# july-10.net
KiCad netlist of a schematic drawn in EAGLE
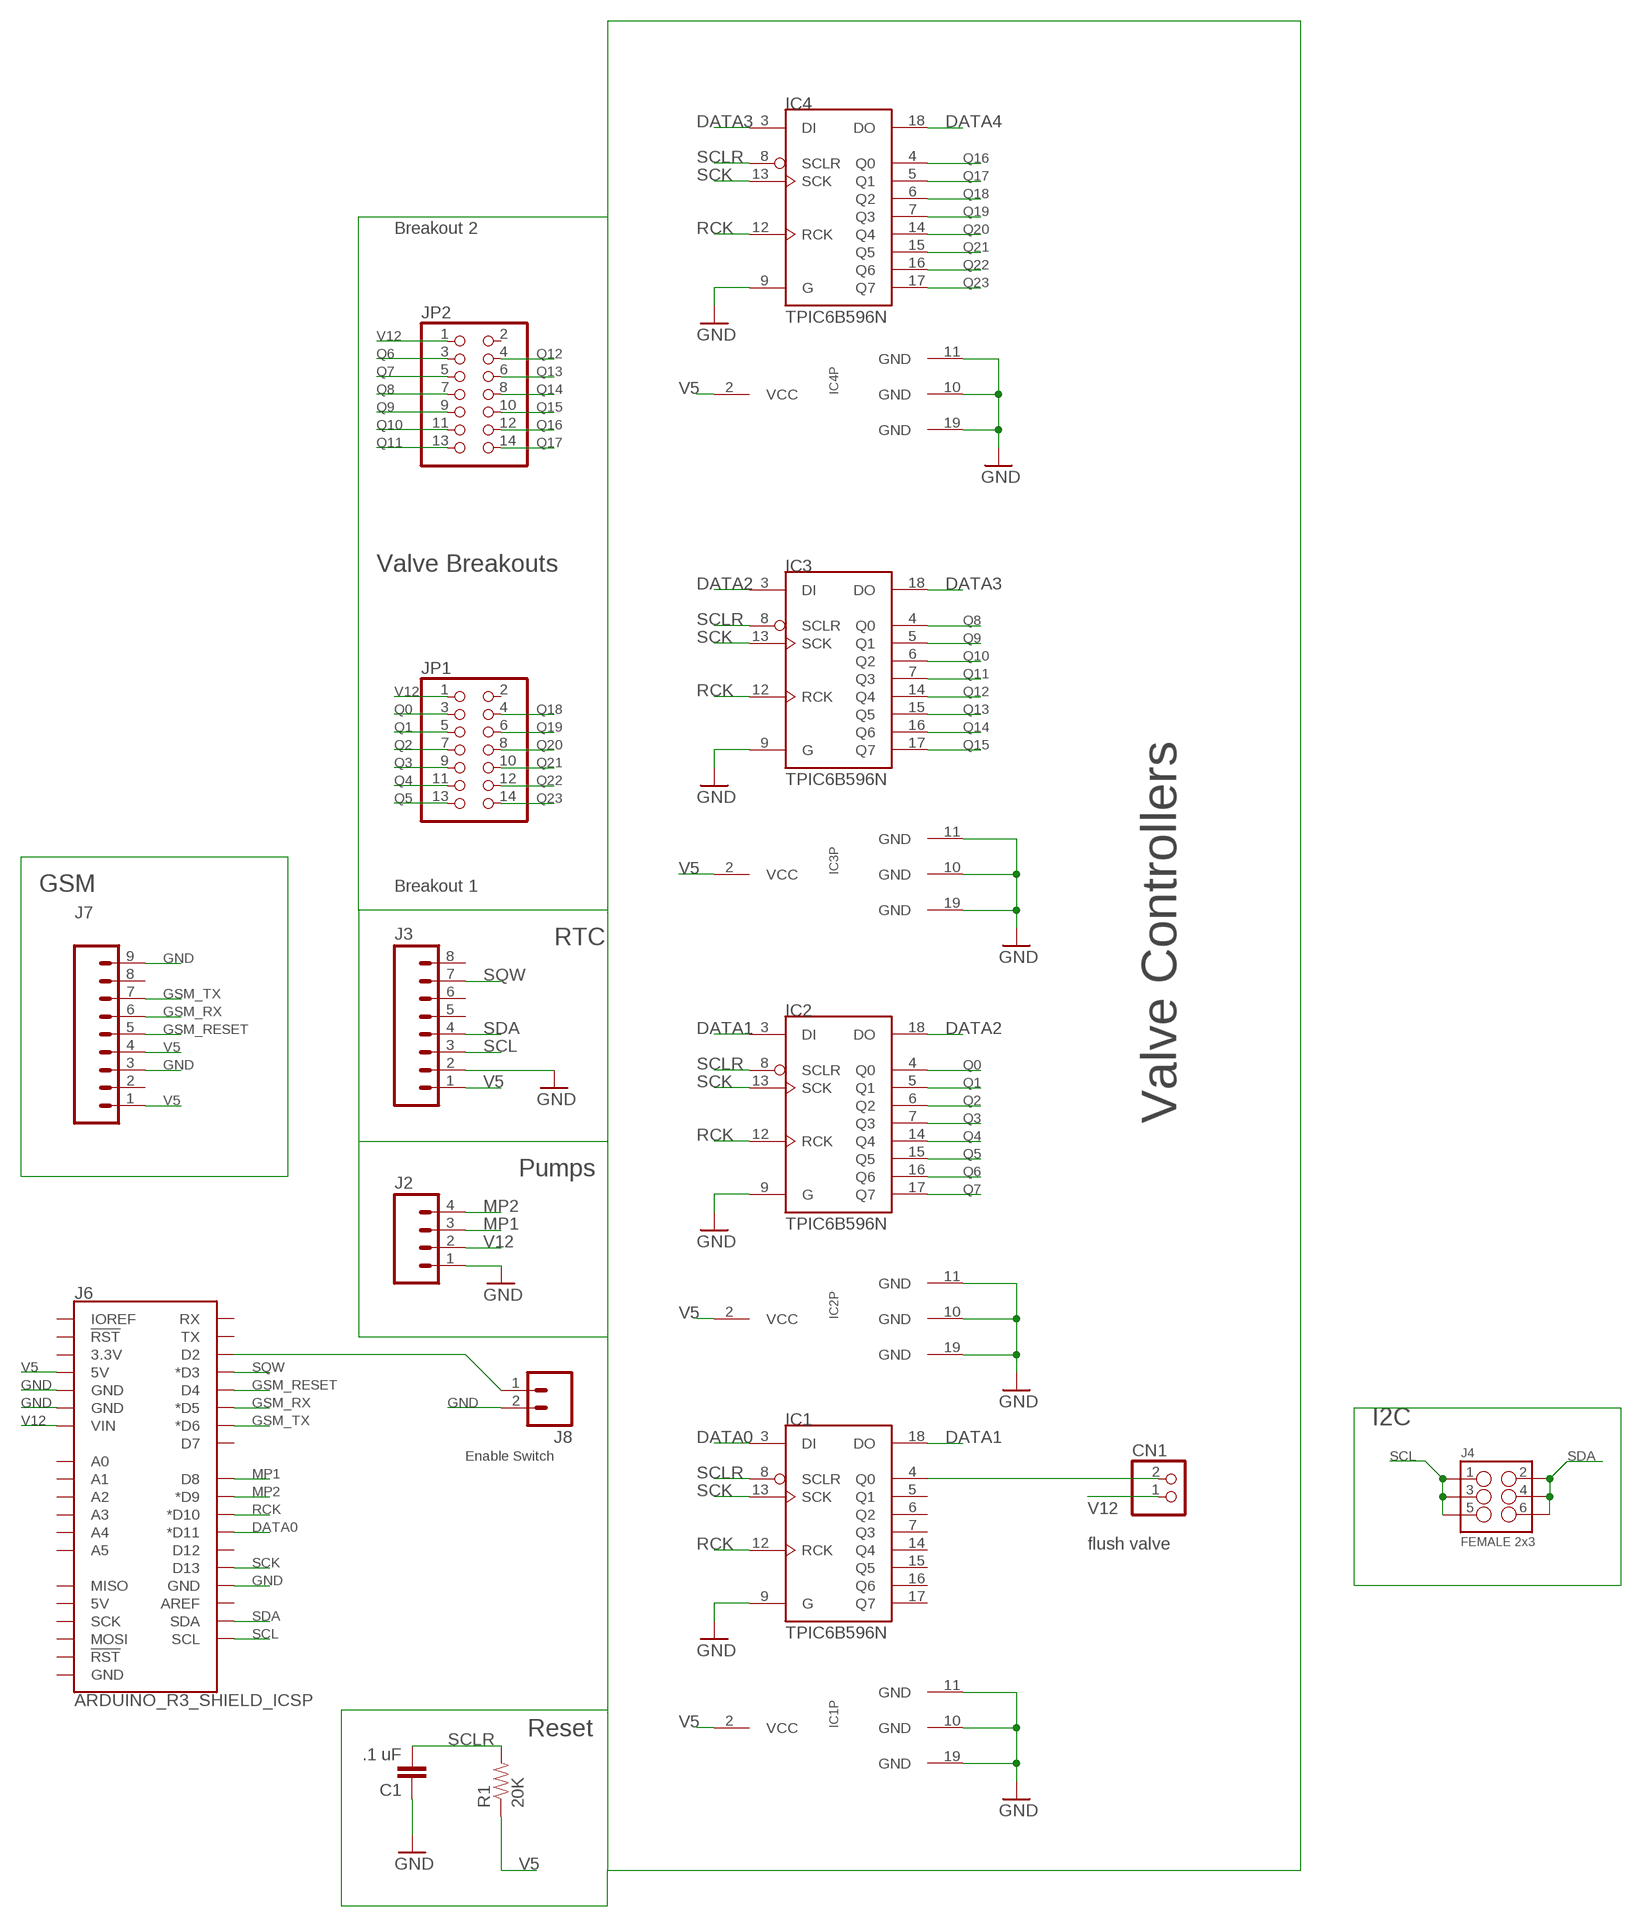
[diagram p0: schematic, sheet 1]

(export (version "E")
  (design (tool "Eeschema 10.0.6"))
  (components
    (comp (ref "C1")
      (value ".1 uF")
      (footprint "eagle-import:AXIAL-5MM")
      (libsource (lib "eagle-import") (part "CAP_"))
    )
    (comp (ref "CN1")
      (value "JST_2PIN-THM")
      (footprint "eagle-import:JST-PH-2-THM")
      (libsource (lib "eagle-import") (part "JST_2PIN-THM"))
    )
    (comp (ref "IC1")
      (value "TPIC6B596N")
      (footprint "eagle-import:DIL20")
      (libsource (lib "eagle-import") (part "TPIC6B596N"))
    )
    (comp (ref "IC2")
      (value "TPIC6B596N")
      (footprint "eagle-import:DIL20")
      (libsource (lib "eagle-import") (part "TPIC6B596N"))
    )
    (comp (ref "IC3")
      (value "TPIC6B596N")
      (footprint "eagle-import:DIL20")
      (libsource (lib "eagle-import") (part "TPIC6B596N"))
    )
    (comp (ref "IC4")
      (value "TPIC6B596N")
      (footprint "eagle-import:DIL20")
      (libsource (lib "eagle-import") (part "TPIC6B596N"))
    )
    (comp (ref "J2")
      (value "M04PTH")
      (footprint "eagle-import:1X04")
      (libsource (lib "eagle-import") (part "M04PTH"))
    )
    (comp (ref "J3")
      (value "M08")
      (footprint "eagle-import:1X08_ROUND")
      (libsource (lib "eagle-import") (part "M08"))
    )
    (comp (ref "J4")
      (value "FEMALE 2x3")
      (footprint "eagle-import:2X3")
      (libsource (lib "eagle-import") (part "M03X2FEMALE"))
    )
    (comp (ref "J6")
      (value "ARDUINO_R3_SHIELD_ICSP")
      (footprint "eagle-import:UNO_R3_SHIELD_ICSP")
      (libsource (lib "eagle-import") (part "ARDUINO_R3_SHIELD_ICSP"))
    )
    (comp (ref "J7")
      (value "M09")
      (footprint "eagle-import:1X09")
      (libsource (lib "eagle-import") (part "M09"))
    )
    (comp (ref "J8")
      (value "M02PTH")
      (footprint "eagle-import:1X02")
      (libsource (lib "eagle-import") (part "M02PTH"))
    )
    (comp (ref "JP1")
      (value "PINHD-2X7")
      (footprint "eagle-import:2X07")
      (libsource (lib "eagle-import") (part "PINHD-2X7"))
    )
    (comp (ref "JP2")
      (value "PINHD-2X7")
      (footprint "eagle-import:2X07")
      (libsource (lib "eagle-import") (part "PINHD-2X7"))
    )
    (comp (ref "R1")
      (value "20K")
      (footprint "eagle-import:AXIAL-0.4")
      (libsource (lib "eagle-import") (part "RESISTORPTH-1/4W"))
    )
  )
  (nets
    (net (code "1") (name "/DATA0") (class "Default")
      (node (ref "IC1") (pin "3") (pinfunction "DI_3") (pintype "input"))
      (node (ref "J6") (pin "D11") (pinfunction "*D11_D11") (pintype "bidirectional"))
    )
    (net (code "2") (name "/DATA1") (class "Default")
      (node (ref "IC1") (pin "18") (pinfunction "DO_18") (pintype "output"))
      (node (ref "IC2") (pin "3") (pinfunction "DI_3") (pintype "input"))
    )
    (net (code "3") (name "/DATA2") (class "Default")
      (node (ref "IC2") (pin "18") (pinfunction "DO_18") (pintype "output"))
      (node (ref "IC3") (pin "3") (pinfunction "DI_3") (pintype "input"))
    )
    (net (code "4") (name "/DATA3") (class "Default")
      (node (ref "IC3") (pin "18") (pinfunction "DO_18") (pintype "output"))
      (node (ref "IC4") (pin "3") (pinfunction "DI_3") (pintype "input"))
    )
    (net (code "5") (name "/DATA4") (class "Default")
      (node (ref "IC4") (pin "18") (pinfunction "DO_18") (pintype "output"))
    )
    (net (code "6") (name "/GSM_RESET") (class "Default")
      (node (ref "J6") (pin "D4") (pinfunction "D4_D4") (pintype "bidirectional"))
      (node (ref "J7") (pin "5") (pinfunction "5_5") (pintype "passive"))
    )
    (net (code "7") (name "/GSM_RX") (class "Default")
      (node (ref "J6") (pin "D5") (pinfunction "*D5_D5") (pintype "bidirectional"))
      (node (ref "J7") (pin "6") (pinfunction "6_6") (pintype "passive"))
    )
    (net (code "8") (name "/GSM_TX") (class "Default")
      (node (ref "J6") (pin "D6") (pinfunction "*D6_D6") (pintype "bidirectional"))
      (node (ref "J7") (pin "7") (pinfunction "7_7") (pintype "passive"))
    )
    (net (code "9") (name "/MP1") (class "Default")
      (node (ref "J2") (pin "3") (pinfunction "3_3") (pintype "passive"))
      (node (ref "J6") (pin "D8") (pinfunction "D8_D8") (pintype "bidirectional"))
    )
    (net (code "10") (name "/MP2") (class "Default")
      (node (ref "J2") (pin "4") (pinfunction "4_4") (pintype "passive"))
      (node (ref "J6") (pin "D9") (pinfunction "*D9_D9") (pintype "bidirectional"))
    )
    (net (code "11") (name "/Q0") (class "Default")
      (node (ref "IC2") (pin "4") (pinfunction "Q0_4") (pintype "open_collector"))
      (node (ref "JP1") (pin "3") (pinfunction "3_3") (pintype "passive"))
    )
    (net (code "12") (name "/Q1") (class "Default")
      (node (ref "IC2") (pin "5") (pinfunction "Q1_5") (pintype "open_collector"))
      (node (ref "JP1") (pin "5") (pinfunction "5_5") (pintype "passive"))
    )
    (net (code "13") (name "/Q2") (class "Default")
      (node (ref "IC2") (pin "6") (pinfunction "Q2_6") (pintype "open_collector"))
      (node (ref "JP1") (pin "7") (pinfunction "7_7") (pintype "passive"))
    )
    (net (code "14") (name "/Q3") (class "Default")
      (node (ref "IC2") (pin "7") (pinfunction "Q3_7") (pintype "open_collector"))
      (node (ref "JP1") (pin "9") (pinfunction "9_9") (pintype "passive"))
    )
    (net (code "15") (name "/Q4") (class "Default")
      (node (ref "IC2") (pin "14") (pinfunction "Q4_14") (pintype "open_collector"))
      (node (ref "JP1") (pin "11") (pinfunction "11_11") (pintype "passive"))
    )
    (net (code "16") (name "/Q5") (class "Default")
      (node (ref "IC2") (pin "15") (pinfunction "Q5_15") (pintype "open_collector"))
      (node (ref "JP1") (pin "13") (pinfunction "13_13") (pintype "passive"))
    )
    (net (code "17") (name "/Q6") (class "Default")
      (node (ref "IC2") (pin "16") (pinfunction "Q6_16") (pintype "open_collector"))
      (node (ref "JP2") (pin "3") (pinfunction "3_3") (pintype "passive"))
    )
    (net (code "18") (name "/Q7") (class "Default")
      (node (ref "IC2") (pin "17") (pinfunction "Q7_17") (pintype "open_collector"))
      (node (ref "JP2") (pin "5") (pinfunction "5_5") (pintype "passive"))
    )
    (net (code "19") (name "/Q8") (class "Default")
      (node (ref "IC3") (pin "4") (pinfunction "Q0_4") (pintype "open_collector"))
      (node (ref "JP2") (pin "7") (pinfunction "7_7") (pintype "passive"))
    )
    (net (code "20") (name "/Q9") (class "Default")
      (node (ref "IC3") (pin "5") (pinfunction "Q1_5") (pintype "open_collector"))
      (node (ref "JP2") (pin "9") (pinfunction "9_9") (pintype "passive"))
    )
    (net (code "21") (name "/Q10") (class "Default")
      (node (ref "IC3") (pin "6") (pinfunction "Q2_6") (pintype "open_collector"))
      (node (ref "JP2") (pin "11") (pinfunction "11_11") (pintype "passive"))
    )
    (net (code "22") (name "/Q11") (class "Default")
      (node (ref "IC3") (pin "7") (pinfunction "Q3_7") (pintype "open_collector"))
      (node (ref "JP2") (pin "13") (pinfunction "13_13") (pintype "passive"))
    )
    (net (code "23") (name "/Q12") (class "Default")
      (node (ref "IC3") (pin "14") (pinfunction "Q4_14") (pintype "open_collector"))
      (node (ref "JP2") (pin "4") (pinfunction "4_4") (pintype "passive"))
    )
    (net (code "24") (name "/Q13") (class "Default")
      (node (ref "IC3") (pin "15") (pinfunction "Q5_15") (pintype "open_collector"))
      (node (ref "JP2") (pin "6") (pinfunction "6_6") (pintype "passive"))
    )
    (net (code "25") (name "/Q14") (class "Default")
      (node (ref "IC3") (pin "16") (pinfunction "Q6_16") (pintype "open_collector"))
      (node (ref "JP2") (pin "8") (pinfunction "8_8") (pintype "passive"))
    )
    (net (code "26") (name "/Q15") (class "Default")
      (node (ref "IC3") (pin "17") (pinfunction "Q7_17") (pintype "open_collector"))
      (node (ref "JP2") (pin "10") (pinfunction "10_10") (pintype "passive"))
    )
    (net (code "27") (name "/Q16") (class "Default")
      (node (ref "IC4") (pin "4") (pinfunction "Q0_4") (pintype "open_collector"))
      (node (ref "JP2") (pin "12") (pinfunction "12_12") (pintype "passive"))
    )
    (net (code "28") (name "/Q17") (class "Default")
      (node (ref "IC4") (pin "5") (pinfunction "Q1_5") (pintype "open_collector"))
      (node (ref "JP2") (pin "14") (pinfunction "14_14") (pintype "passive"))
    )
    (net (code "29") (name "/Q18") (class "Default")
      (node (ref "IC4") (pin "6") (pinfunction "Q2_6") (pintype "open_collector"))
      (node (ref "JP1") (pin "4") (pinfunction "4_4") (pintype "passive"))
    )
    (net (code "30") (name "/Q19") (class "Default")
      (node (ref "IC4") (pin "7") (pinfunction "Q3_7") (pintype "open_collector"))
      (node (ref "JP1") (pin "6") (pinfunction "6_6") (pintype "passive"))
    )
    (net (code "31") (name "/Q20") (class "Default")
      (node (ref "IC4") (pin "14") (pinfunction "Q4_14") (pintype "open_collector"))
      (node (ref "JP1") (pin "8") (pinfunction "8_8") (pintype "passive"))
    )
    (net (code "32") (name "/Q21") (class "Default")
      (node (ref "IC4") (pin "15") (pinfunction "Q5_15") (pintype "open_collector"))
      (node (ref "JP1") (pin "10") (pinfunction "10_10") (pintype "passive"))
    )
    (net (code "33") (name "/Q22") (class "Default")
      (node (ref "IC4") (pin "16") (pinfunction "Q6_16") (pintype "open_collector"))
      (node (ref "JP1") (pin "12") (pinfunction "12_12") (pintype "passive"))
    )
    (net (code "34") (name "/Q23") (class "Default")
      (node (ref "IC4") (pin "17") (pinfunction "Q7_17") (pintype "open_collector"))
      (node (ref "JP1") (pin "14") (pinfunction "14_14") (pintype "passive"))
    )
    (net (code "35") (name "/RCK") (class "Default")
      (node (ref "IC1") (pin "12") (pinfunction "RCK_12") (pintype "input"))
      (node (ref "IC2") (pin "12") (pinfunction "RCK_12") (pintype "input"))
      (node (ref "IC3") (pin "12") (pinfunction "RCK_12") (pintype "input"))
      (node (ref "IC4") (pin "12") (pinfunction "RCK_12") (pintype "input"))
      (node (ref "J6") (pin "D10") (pinfunction "*D10_D10") (pintype "bidirectional"))
    )
    (net (code "36") (name "/SCK") (class "Default")
      (node (ref "IC1") (pin "13") (pinfunction "SCK_13") (pintype "input"))
      (node (ref "IC2") (pin "13") (pinfunction "SCK_13") (pintype "input"))
      (node (ref "IC3") (pin "13") (pinfunction "SCK_13") (pintype "input"))
      (node (ref "IC4") (pin "13") (pinfunction "SCK_13") (pintype "input"))
      (node (ref "J6") (pin "D13") (pinfunction "D13_D13") (pintype "bidirectional"))
    )
    (net (code "37") (name "/SCL") (class "Default")
      (node (ref "J3") (pin "3") (pinfunction "3_3") (pintype "passive"))
      (node (ref "J4") (pin "1") (pinfunction "1_1") (pintype "bidirectional"))
      (node (ref "J4") (pin "3") (pinfunction "3_3") (pintype "bidirectional"))
      (node (ref "J4") (pin "5") (pinfunction "5_5") (pintype "bidirectional"))
      (node (ref "J6") (pin "SCL") (pinfunction "SCL_SCL") (pintype "bidirectional"))
    )
    (net (code "38") (name "/SCLR") (class "Default")
      (node (ref "C1") (pin "P$2") (pinfunction "2_P$2") (pintype "passive"))
      (node (ref "IC1") (pin "8") (pinfunction "SCLR_8") (pintype "input"))
      (node (ref "IC2") (pin "8") (pinfunction "SCLR_8") (pintype "input"))
      (node (ref "IC3") (pin "8") (pinfunction "SCLR_8") (pintype "input"))
      (node (ref "IC4") (pin "8") (pinfunction "SCLR_8") (pintype "input"))
      (node (ref "R1") (pin "P$2") (pinfunction "2_P$2") (pintype "passive"))
    )
    (net (code "39") (name "/SDA") (class "Default")
      (node (ref "J3") (pin "4") (pinfunction "4_4") (pintype "passive"))
      (node (ref "J4") (pin "2") (pinfunction "2_2") (pintype "bidirectional"))
      (node (ref "J4") (pin "4") (pinfunction "4_4") (pintype "bidirectional"))
      (node (ref "J4") (pin "6") (pinfunction "6_6") (pintype "bidirectional"))
      (node (ref "J6") (pin "SDA") (pinfunction "SDA_SDA") (pintype "bidirectional"))
    )
    (net (code "40") (name "/SQW") (class "Default")
      (node (ref "J3") (pin "7") (pinfunction "7_7") (pintype "passive"))
      (node (ref "J6") (pin "D3") (pinfunction "*D3_D3") (pintype "bidirectional"))
    )
    (net (code "41") (name "/V5") (class "Default")
      (node (ref "IC1") (pin "2") (pinfunction "VCC_2") (pintype "power_in"))
      (node (ref "IC2") (pin "2") (pinfunction "VCC_2") (pintype "power_in"))
      (node (ref "IC3") (pin "2") (pinfunction "VCC_2") (pintype "power_in"))
      (node (ref "IC4") (pin "2") (pinfunction "VCC_2") (pintype "power_in"))
      (node (ref "J3") (pin "1") (pinfunction "1_1") (pintype "passive"))
      (node (ref "J6") (pin "5V") (pinfunction "5V_5V") (pintype "bidirectional"))
      (node (ref "J7") (pin "1") (pinfunction "1_1") (pintype "passive"))
      (node (ref "J7") (pin "4") (pinfunction "4_4") (pintype "passive"))
      (node (ref "R1") (pin "P$1") (pinfunction "1_P$1") (pintype "passive"))
    )
    (net (code "42") (name "/V12") (class "Default")
      (node (ref "CN1") (pin "1") (pinfunction "2_1") (pintype "passive"))
      (node (ref "J2") (pin "2") (pinfunction "2_2") (pintype "passive"))
      (node (ref "J6") (pin "VIN") (pinfunction "VIN_VIN") (pintype "bidirectional"))
      (node (ref "JP1") (pin "1") (pinfunction "1_1") (pintype "passive"))
      (node (ref "JP2") (pin "1") (pinfunction "1_1") (pintype "passive"))
    )
    (net (code "43") (name "GND") (class "Default")
      (node (ref "C1") (pin "P$1") (pinfunction "1_P$1") (pintype "passive"))
      (node (ref "IC1") (pin "10") (pinfunction "GND_10") (pintype "power_in"))
      (node (ref "IC1") (pin "11") (pinfunction "GND_11") (pintype "power_in"))
      (node (ref "IC1") (pin "19") (pinfunction "GND_19") (pintype "power_in"))
      (node (ref "IC1") (pin "9") (pinfunction "G_9") (pintype "input"))
      (node (ref "IC2") (pin "10") (pinfunction "GND_10") (pintype "power_in"))
      (node (ref "IC2") (pin "11") (pinfunction "GND_11") (pintype "power_in"))
      (node (ref "IC2") (pin "19") (pinfunction "GND_19") (pintype "power_in"))
      (node (ref "IC2") (pin "9") (pinfunction "G_9") (pintype "input"))
      (node (ref "IC3") (pin "10") (pinfunction "GND_10") (pintype "power_in"))
      (node (ref "IC3") (pin "11") (pinfunction "GND_11") (pintype "power_in"))
      (node (ref "IC3") (pin "19") (pinfunction "GND_19") (pintype "power_in"))
      (node (ref "IC3") (pin "9") (pinfunction "G_9") (pintype "input"))
      (node (ref "IC4") (pin "10") (pinfunction "GND_10") (pintype "power_in"))
      (node (ref "IC4") (pin "11") (pinfunction "GND_11") (pintype "power_in"))
      (node (ref "IC4") (pin "19") (pinfunction "GND_19") (pintype "power_in"))
      (node (ref "IC4") (pin "9") (pinfunction "G_9") (pintype "input"))
      (node (ref "J2") (pin "1") (pinfunction "1_1") (pintype "passive"))
      (node (ref "J3") (pin "2") (pinfunction "2_2") (pintype "passive"))
      (node (ref "J6") (pin "GND@0") (pinfunction "GND_GND@0") (pintype "bidirectional"))
      (node (ref "J6") (pin "GND@1") (pinfunction "GND_GND@1") (pintype "bidirectional"))
      (node (ref "J6") (pin "GND@2") (pinfunction "GND_GND@2") (pintype "bidirectional"))
      (node (ref "J7") (pin "3") (pinfunction "3_3") (pintype "passive"))
      (node (ref "J7") (pin "9") (pinfunction "9_9") (pintype "passive"))
      (node (ref "J8") (pin "2") (pinfunction "2_2") (pintype "passive"))
    )
    (net (code "44") (name "Net-(CN1-1)") (class "Default")
      (node (ref "CN1") (pin "2") (pinfunction "1_2") (pintype "passive"))
      (node (ref "IC1") (pin "4") (pinfunction "Q0_4") (pintype "open_collector"))
    )
    (net (code "45") (name "Net-(J6-PadD2)") (class "Default")
      (node (ref "J6") (pin "D2") (pinfunction "D2_D2") (pintype "bidirectional"))
      (node (ref "J8") (pin "1") (pinfunction "1_1") (pintype "passive"))
    )
    (net (code "46") (name "unconnected-(IC1A-Q1-Pad5)") (class "Default")
      (node (ref "IC1") (pin "5") (pinfunction "Q1_5") (pintype "open_collector"))
    )
    (net (code "47") (name "unconnected-(IC1A-Q2-Pad6)") (class "Default")
      (node (ref "IC1") (pin "6") (pinfunction "Q2_6") (pintype "open_collector"))
    )
    (net (code "48") (name "unconnected-(IC1A-Q3-Pad7)") (class "Default")
      (node (ref "IC1") (pin "7") (pinfunction "Q3_7") (pintype "open_collector"))
    )
    (net (code "49") (name "unconnected-(IC1A-Q4-Pad14)") (class "Default")
      (node (ref "IC1") (pin "14") (pinfunction "Q4_14") (pintype "open_collector"))
    )
    (net (code "50") (name "unconnected-(IC1A-Q5-Pad15)") (class "Default")
      (node (ref "IC1") (pin "15") (pinfunction "Q5_15") (pintype "open_collector"))
    )
    (net (code "51") (name "unconnected-(IC1A-Q6-Pad16)") (class "Default")
      (node (ref "IC1") (pin "16") (pinfunction "Q6_16") (pintype "open_collector"))
    )
    (net (code "52") (name "unconnected-(IC1A-Q7-Pad17)") (class "Default")
      (node (ref "IC1") (pin "17") (pinfunction "Q7_17") (pintype "open_collector"))
    )
    (net (code "53") (name "unconnected-(J3-Pad5)") (class "Default")
      (node (ref "J3") (pin "5") (pinfunction "5_5") (pintype "passive"))
    )
    (net (code "54") (name "unconnected-(J3-Pad6)") (class "Default")
      (node (ref "J3") (pin "6") (pinfunction "6_6") (pintype "passive"))
    )
    (net (code "55") (name "unconnected-(J3-Pad8)") (class "Default")
      (node (ref "J3") (pin "8") (pinfunction "8_8") (pintype "passive"))
    )
    (net (code "56") (name "unconnected-(J6-5V-Pad5V_ICSP)") (class "Default")
      (node (ref "J6") (pin "5V_ICSP") (pinfunction "5V_5V_ICSP") (pintype "bidirectional"))
    )
    (net (code "57") (name "unconnected-(J6-GND-PadGND_ICSP)") (class "Default")
      (node (ref "J6") (pin "GND_ICSP") (pinfunction "GND_GND_ICSP") (pintype "bidirectional"))
    )
    (net (code "58") (name "unconnected-(J6-Pad3.3V)") (class "Default")
      (node (ref "J6") (pin "3.3V") (pinfunction "3.3V_3.3V") (pintype "bidirectional"))
    )
    (net (code "59") (name "unconnected-(J6-PadA0)") (class "Default")
      (node (ref "J6") (pin "A0") (pinfunction "A0_A0") (pintype "bidirectional"))
    )
    (net (code "60") (name "unconnected-(J6-PadA1)") (class "Default")
      (node (ref "J6") (pin "A1") (pinfunction "A1_A1") (pintype "bidirectional"))
    )
    (net (code "61") (name "unconnected-(J6-PadA2)") (class "Default")
      (node (ref "J6") (pin "A2") (pinfunction "A2_A2") (pintype "bidirectional"))
    )
    (net (code "62") (name "unconnected-(J6-PadA3)") (class "Default")
      (node (ref "J6") (pin "A3") (pinfunction "A3_A3") (pintype "bidirectional"))
    )
    (net (code "63") (name "unconnected-(J6-PadA4)") (class "Default")
      (node (ref "J6") (pin "A4") (pinfunction "A4_A4") (pintype "bidirectional"))
    )
    (net (code "64") (name "unconnected-(J6-PadA5)") (class "Default")
      (node (ref "J6") (pin "A5") (pinfunction "A5_A5") (pintype "bidirectional"))
    )
    (net (code "65") (name "unconnected-(J6-PadAREF)") (class "Default")
      (node (ref "J6") (pin "AREF") (pinfunction "AREF_AREF") (pintype "bidirectional"))
    )
    (net (code "66") (name "unconnected-(J6-PadD7)") (class "Default")
      (node (ref "J6") (pin "D7") (pinfunction "D7_D7") (pintype "bidirectional"))
    )
    (net (code "67") (name "unconnected-(J6-PadD12)") (class "Default")
      (node (ref "J6") (pin "D12") (pinfunction "D12_D12") (pintype "bidirectional"))
    )
    (net (code "68") (name "unconnected-(J6-PadIOREF)") (class "Default")
      (node (ref "J6") (pin "IOREF") (pinfunction "IOREF_IOREF") (pintype "bidirectional"))
    )
    (net (code "69") (name "unconnected-(J6-PadMISO)") (class "Default")
      (node (ref "J6") (pin "MISO") (pinfunction "MISO_MISO") (pintype "bidirectional"))
    )
    (net (code "70") (name "unconnected-(J6-PadMOSI)") (class "Default")
      (node (ref "J6") (pin "MOSI") (pinfunction "MOSI_MOSI") (pintype "bidirectional"))
    )
    (net (code "71") (name "unconnected-(J6-PadRX)") (class "Default")
      (node (ref "J6") (pin "RX") (pinfunction "RX_RX") (pintype "bidirectional"))
    )
    (net (code "72") (name "unconnected-(J6-PadSCK)") (class "Default")
      (node (ref "J6") (pin "SCK") (pinfunction "SCK_SCK") (pintype "bidirectional"))
    )
    (net (code "73") (name "unconnected-(J6-PadTX)") (class "Default")
      (node (ref "J6") (pin "TX") (pinfunction "TX_TX") (pintype "bidirectional"))
    )
    (net (code "74") (name "unconnected-(J6-~{RST}-PadRES)") (class "Default")
      (node (ref "J6") (pin "RES") (pinfunction "~{RST}_RES") (pintype "bidirectional"))
    )
    (net (code "75") (name "unconnected-(J6-~{RST}-PadRST_ICSP)") (class "Default")
      (node (ref "J6") (pin "RST_ICSP") (pinfunction "~{RST}_RST_ICSP") (pintype "bidirectional"))
    )
    (net (code "76") (name "unconnected-(J7-Pad2)") (class "Default")
      (node (ref "J7") (pin "2") (pinfunction "2_2") (pintype "passive"))
    )
    (net (code "77") (name "unconnected-(J7-Pad8)") (class "Default")
      (node (ref "J7") (pin "8") (pinfunction "8_8") (pintype "passive"))
    )
    (net (code "78") (name "unconnected-(JP1-Pad2)") (class "Default")
      (node (ref "JP1") (pin "2") (pinfunction "2_2") (pintype "passive"))
    )
    (net (code "79") (name "unconnected-(JP2-Pad2)") (class "Default")
      (node (ref "JP2") (pin "2") (pinfunction "2_2") (pintype "passive"))
    )
  )
)
